# 4-up.net
KiCad netlist of a schematic drawn in EAGLE
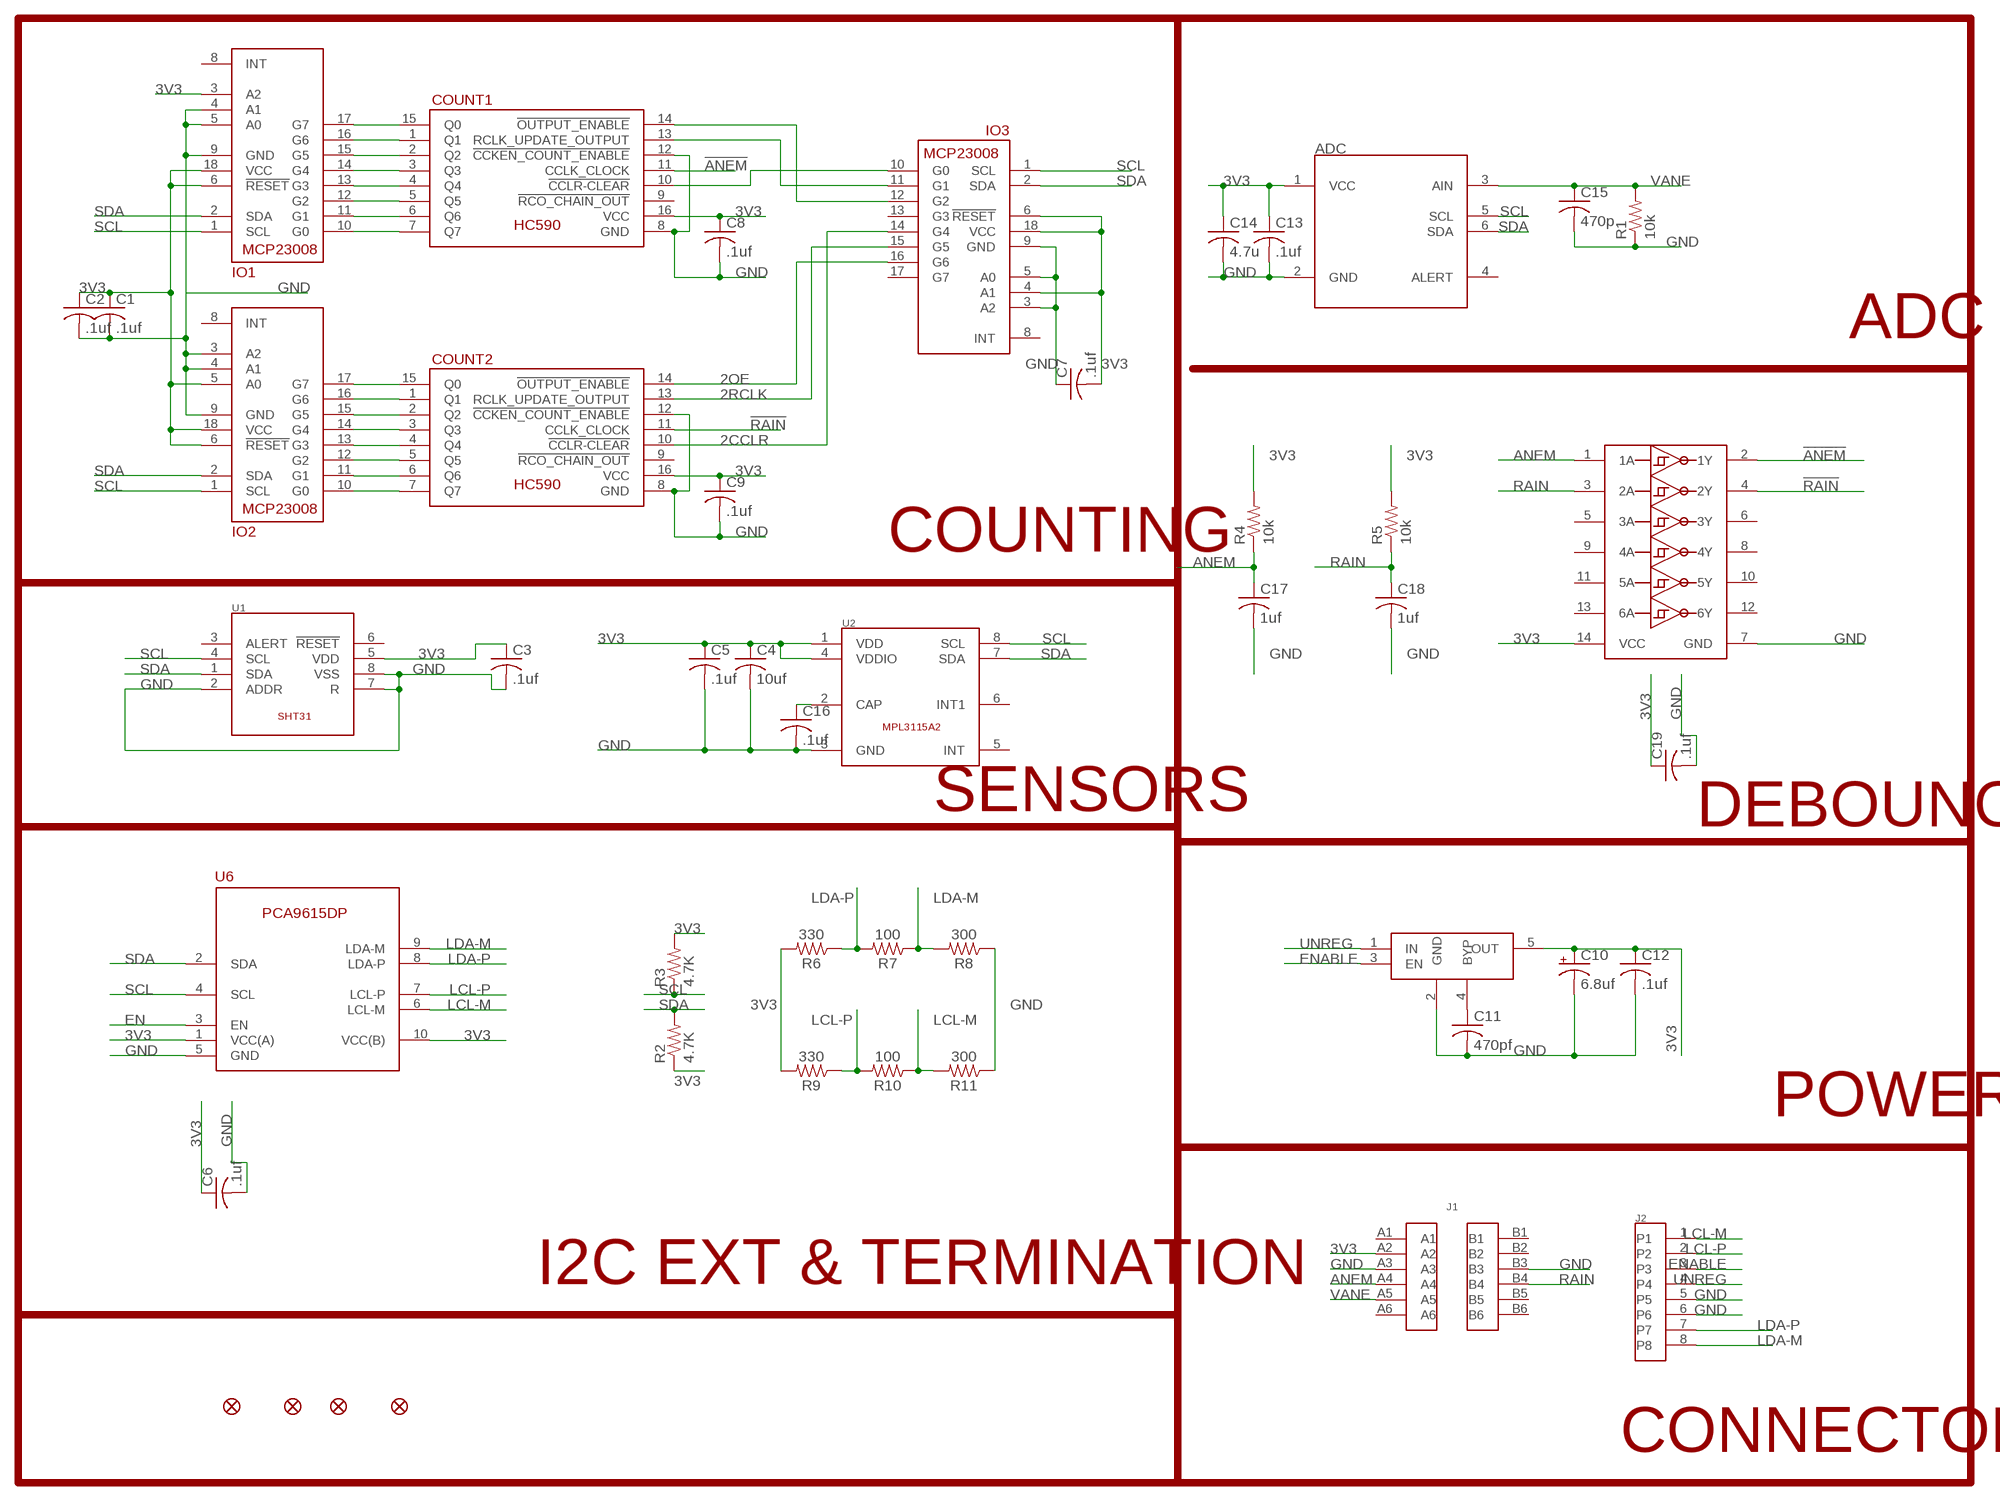
[diagram p0: schematic, sheet 1]

(export (version "E")
  (design (tool "Eeschema 10.0.6"))
  (components
    (comp (ref "ADC")
      (value "ADC081C021SOT-DDC")
      (footprint "eagle-import:SOP95P280X110-6")
      (libsource (lib "eagle-import") (part "ADC081C021SOT-DDC"))
    )
    (comp (ref "C1")
      (value ".1uf")
      (footprint "eagle-import:C0603K")
      (libsource (lib "eagle-import") (part "C-USC0603K"))
    )
    (comp (ref "C2")
      (value ".1uf")
      (footprint "eagle-import:C0603K")
      (libsource (lib "eagle-import") (part "C-USC0603K"))
    )
    (comp (ref "C3")
      (value ".1uf")
      (footprint "eagle-import:C0603K")
      (libsource (lib "eagle-import") (part "C-USC0603K"))
    )
    (comp (ref "C4")
      (value "10uf")
      (footprint "eagle-import:C0603K")
      (libsource (lib "eagle-import") (part "C-USC0603K"))
    )
    (comp (ref "C5")
      (value ".1uf")
      (footprint "eagle-import:C0603K")
      (libsource (lib "eagle-import") (part "C-USC0603K"))
    )
    (comp (ref "C6")
      (value ".1uf")
      (footprint "eagle-import:C0603K")
      (libsource (lib "eagle-import") (part "C-USC0603K"))
    )
    (comp (ref "C7")
      (value ".1uf")
      (footprint "eagle-import:C0603K")
      (libsource (lib "eagle-import") (part "C-USC0603K"))
    )
    (comp (ref "C8")
      (value ".1uf")
      (footprint "eagle-import:C0603K")
      (libsource (lib "eagle-import") (part "C-USC0603K"))
    )
    (comp (ref "C9")
      (value ".1uf")
      (footprint "eagle-import:C0603K")
      (libsource (lib "eagle-import") (part "C-USC0603K"))
    )
    (comp (ref "C10")
      (value "6.8uf")
      (footprint "eagle-import:A_3216-18R")
      (libsource (lib "eagle-import") (part "CPOL-USA/3216-18R"))
    )
    (comp (ref "C11")
      (value "470pf")
      (footprint "eagle-import:C0603K")
      (libsource (lib "eagle-import") (part "C-USC0603K"))
    )
    (comp (ref "C12")
      (value ".1uf")
      (footprint "eagle-import:C0603K")
      (libsource (lib "eagle-import") (part "C-USC0603K"))
    )
    (comp (ref "C13")
      (value ".1uf")
      (footprint "eagle-import:C0603K")
      (libsource (lib "eagle-import") (part "C-USC0603K"))
    )
    (comp (ref "C14")
      (value "4.7u")
      (footprint "eagle-import:C0603K")
      (libsource (lib "eagle-import") (part "C-USC0603K"))
    )
    (comp (ref "C15")
      (value "470p")
      (footprint "eagle-import:C0603K")
      (libsource (lib "eagle-import") (part "C-USC0603K"))
    )
    (comp (ref "C16")
      (value ".1uf")
      (footprint "eagle-import:C0603K")
      (libsource (lib "eagle-import") (part "C-USC0603K"))
    )
    (comp (ref "C17")
      (value "1uf")
      (footprint "eagle-import:C0603K")
      (libsource (lib "eagle-import") (part "C-USC0603K"))
    )
    (comp (ref "C18")
      (value "1uf")
      (footprint "eagle-import:C0603K")
      (libsource (lib "eagle-import") (part "C-USC0603K"))
    )
    (comp (ref "C19")
      (value ".1uf")
      (footprint "eagle-import:C0603K")
      (libsource (lib "eagle-import") (part "C-USC0603K"))
    )
    (comp (ref "COUNT1")
      (value "74HC590")
      (footprint "eagle-import:SOIC127P1050X265-16")
      (libsource (lib "eagle-import") (part "74HC590"))
    )
    (comp (ref "COUNT2")
      (value "74HC590")
      (footprint "eagle-import:SOIC127P1050X265-16")
      (libsource (lib "eagle-import") (part "74HC590"))
    )
    (comp (ref "FID1")
      (value "FIDUCIAL1X2.5")
      (footprint "eagle-import:FIDUCIAL-1X2.5")
      (libsource (lib "eagle-import") (part "FIDUCIAL1X2.5"))
    )
    (comp (ref "FID2")
      (value "FIDUCIAL1X2.5")
      (footprint "eagle-import:FIDUCIAL-1X2.5")
      (libsource (lib "eagle-import") (part "FIDUCIAL1X2.5"))
    )
    (comp (ref "FID3")
      (value "FIDUCIAL1X2.5")
      (footprint "eagle-import:FIDUCIAL-1X2.5")
      (libsource (lib "eagle-import") (part "FIDUCIAL1X2.5"))
    )
    (comp (ref "FID4")
      (value "FIDUCIAL1X2.5")
      (footprint "eagle-import:FIDUCIAL-1X2.5")
      (libsource (lib "eagle-import") (part "FIDUCIAL1X2.5"))
    )
    (comp (ref "INVERTER")
      (value "74HC14")
      (footprint "eagle-import:SOIC127P780X200-14")
      (libsource (lib "eagle-import") (part "74HC14"))
    )
    (comp (ref "IO1")
      (value "MCP23008")
      (footprint "eagle-import:SOIC18-W")
      (libsource (lib "eagle-import") (part "MCP23008"))
    )
    (comp (ref "IO2")
      (value "MCP23008")
      (footprint "eagle-import:SOIC18-W")
      (libsource (lib "eagle-import") (part "MCP23008"))
    )
    (comp (ref "IO3")
      (value "MCP23008")
      (footprint "eagle-import:SOIC18-W")
      (libsource (lib "eagle-import") (part "MCP23008"))
    )
    (comp (ref "J1")
      (value "43841-0005")
      (footprint "eagle-import:43841-0005")
      (libsource (lib "eagle-import") (part "43841-0005"))
    )
    (comp (ref "J2")
      (value "95501-6889")
      (footprint "eagle-import:95501-6889")
      (libsource (lib "eagle-import") (part "95501-6889"))
    )
    (comp (ref "R1")
      (value "10k")
      (footprint "eagle-import:R0603")
      (libsource (lib "eagle-import") (part "R-US_R0603"))
    )
    (comp (ref "R2")
      (value "4.7K")
      (footprint "eagle-import:R0603")
      (libsource (lib "eagle-import") (part "R-US_R0603"))
    )
    (comp (ref "R3")
      (value "4.7K")
      (footprint "eagle-import:R0603")
      (libsource (lib "eagle-import") (part "R-US_R0603"))
    )
    (comp (ref "R4")
      (value "10k")
      (footprint "eagle-import:R0603")
      (libsource (lib "eagle-import") (part "R-US_R0603"))
    )
    (comp (ref "R5")
      (value "10k")
      (footprint "eagle-import:R0603")
      (libsource (lib "eagle-import") (part "R-US_R0603"))
    )
    (comp (ref "R6")
      (value "330")
      (footprint "eagle-import:0603")
      (libsource (lib "eagle-import") (part "100KOHM-0603-1/10W-1%"))
    )
    (comp (ref "R7")
      (value "100")
      (footprint "eagle-import:0603")
      (libsource (lib "eagle-import") (part "100KOHM-0603-1/10W-1%"))
    )
    (comp (ref "R8")
      (value "300")
      (footprint "eagle-import:0603")
      (libsource (lib "eagle-import") (part "100KOHM-0603-1/10W-1%"))
    )
    (comp (ref "R9")
      (value "330")
      (footprint "eagle-import:0603")
      (libsource (lib "eagle-import") (part "100KOHM-0603-1/10W-1%"))
    )
    (comp (ref "R10")
      (value "100")
      (footprint "eagle-import:0603")
      (libsource (lib "eagle-import") (part "100KOHM-0603-1/10W-1%"))
    )
    (comp (ref "R11")
      (value "300")
      (footprint "eagle-import:0603")
      (libsource (lib "eagle-import") (part "100KOHM-0603-1/10W-1%"))
    )
    (comp (ref "U1")
      (value "SHT31")
      (footprint "eagle-import:SON50P240X240X80-9T80")
      (libsource (lib "eagle-import") (part "SHT31"))
    )
    (comp (ref "U2")
      (value "MPL3115A2LGA8")
      (footprint "eagle-import:SON125P300X500X110-8")
      (libsource (lib "eagle-import") (part "MPL3115A2LGA8"))
    )
    (comp (ref "U5")
      (value "MIC5219-3.3YM5-TR")
      (footprint "eagle-import:SOT95P280X145-5")
      (libsource (lib "eagle-import") (part "MIC5219-3.3YM5-TR"))
    )
    (comp (ref "U6")
      (value "PCA9615")
      (footprint "eagle-import:SOP50P490X110-10")
      (libsource (lib "eagle-import") (part "PCA9615"))
    )
  )
  (nets
    (net (code "1") (name "/2CCLR") (class "Default")
      (node (ref "COUNT2") (pin "10") (pinfunction "~{CCLR-CLEAR}_10") (pintype "bidirectional"))
      (node (ref "IO3") (pin "14") (pinfunction "G4_14") (pintype "bidirectional"))
    )
    (net (code "2") (name "/2OE") (class "Default")
      (node (ref "COUNT2") (pin "14") (pinfunction "~{OUTPUT_ENABLE}_14") (pintype "bidirectional"))
      (node (ref "IO3") (pin "16") (pinfunction "G6_16") (pintype "bidirectional"))
    )
    (net (code "3") (name "/2RCLK") (class "Default")
      (node (ref "COUNT2") (pin "13") (pinfunction "RCLK_UPDATE_OUTPUT_13") (pintype "bidirectional"))
      (node (ref "IO3") (pin "15") (pinfunction "G5_15") (pintype "bidirectional"))
    )
    (net (code "4") (name "/3V3") (class "Default")
      (node (ref "ADC") (pin "1") (pinfunction "VCC_1") (pintype "bidirectional"))
      (node (ref "C1") (pin "1") (pinfunction "1_1") (pintype "passive"))
      (node (ref "C10") (pin "+") (pinfunction "+_+") (pintype "passive"))
      (node (ref "C12") (pin "1") (pinfunction "1_1") (pintype "passive"))
      (node (ref "C13") (pin "1") (pinfunction "1_1") (pintype "passive"))
      (node (ref "C14") (pin "1") (pinfunction "1_1") (pintype "passive"))
      (node (ref "C19") (pin "1") (pinfunction "1_1") (pintype "passive"))
      (node (ref "C2") (pin "1") (pinfunction "1_1") (pintype "passive"))
      (node (ref "C3") (pin "1") (pinfunction "1_1") (pintype "passive"))
      (node (ref "C4") (pin "1") (pinfunction "1_1") (pintype "passive"))
      (node (ref "C5") (pin "1") (pinfunction "1_1") (pintype "passive"))
      (node (ref "C6") (pin "1") (pinfunction "1_1") (pintype "passive"))
      (node (ref "C7") (pin "2") (pinfunction "2_2") (pintype "passive"))
      (node (ref "C8") (pin "1") (pinfunction "1_1") (pintype "passive"))
      (node (ref "C9") (pin "1") (pinfunction "1_1") (pintype "passive"))
      (node (ref "COUNT1") (pin "16") (pinfunction "VCC_16") (pintype "bidirectional"))
      (node (ref "COUNT2") (pin "16") (pinfunction "VCC_16") (pintype "bidirectional"))
      (node (ref "INVERTER") (pin "14") (pinfunction "VCC_14") (pintype "bidirectional"))
      (node (ref "IO1") (pin "18") (pinfunction "VCC_18") (pintype "bidirectional"))
      (node (ref "IO1") (pin "3") (pinfunction "A2_3") (pintype "bidirectional"))
      (node (ref "IO1") (pin "6") (pinfunction "~{RESET}_6") (pintype "bidirectional"))
      (node (ref "IO2") (pin "18") (pinfunction "VCC_18") (pintype "bidirectional"))
      (node (ref "IO2") (pin "5") (pinfunction "A0_5") (pintype "bidirectional"))
      (node (ref "IO2") (pin "6") (pinfunction "~{RESET}_6") (pintype "bidirectional"))
      (node (ref "IO3") (pin "18") (pinfunction "VCC_18") (pintype "bidirectional"))
      (node (ref "IO3") (pin "4") (pinfunction "A1_4") (pintype "bidirectional"))
      (node (ref "IO3") (pin "6") (pinfunction "~{RESET}_6") (pintype "bidirectional"))
      (node (ref "J1") (pin "A2") (pinfunction "A2_A2") (pintype "bidirectional"))
      (node (ref "R2") (pin "1") (pinfunction "1_1") (pintype "passive"))
      (node (ref "R3") (pin "2") (pinfunction "2_2") (pintype "passive"))
      (node (ref "R4") (pin "2") (pinfunction "2_2") (pintype "passive"))
      (node (ref "R5") (pin "2") (pinfunction "2_2") (pintype "passive"))
      (node (ref "R6") (pin "2") (pinfunction "2_2") (pintype "passive"))
      (node (ref "R9") (pin "2") (pinfunction "2_2") (pintype "passive"))
      (node (ref "U1") (pin "5") (pinfunction "VDD_5") (pintype "bidirectional"))
      (node (ref "U2") (pin "1") (pinfunction "VDD_1") (pintype "bidirectional"))
      (node (ref "U2") (pin "4") (pinfunction "VDDIO_4") (pintype "bidirectional"))
      (node (ref "U5") (pin "5") (pinfunction "OUT_5") (pintype "bidirectional"))
      (node (ref "U6") (pin "1") (pinfunction "VCC(A)_1") (pintype "bidirectional"))
      (node (ref "U6") (pin "10") (pinfunction "VCC(B)_10") (pintype "bidirectional"))
    )
    (net (code "5") (name "/ANEM") (class "Default")
      (node (ref "C17") (pin "1") (pinfunction "1_1") (pintype "passive"))
      (node (ref "INVERTER") (pin "1") (pinfunction "1A_1") (pintype "bidirectional"))
      (node (ref "J1") (pin "A4") (pinfunction "A4_A4") (pintype "bidirectional"))
      (node (ref "R4") (pin "1") (pinfunction "1_1") (pintype "passive"))
    )
    (net (code "6") (name "/EN") (class "Default")
      (node (ref "U6") (pin "3") (pinfunction "EN_3") (pintype "bidirectional"))
    )
    (net (code "7") (name "/ENABLE") (class "Default")
      (node (ref "J2") (pin "3") (pinfunction "P3_3") (pintype "bidirectional"))
      (node (ref "U5") (pin "3") (pinfunction "EN_3") (pintype "bidirectional"))
    )
    (net (code "8") (name "/GND") (class "Default")
      (node (ref "ADC") (pin "2") (pinfunction "GND_2") (pintype "bidirectional"))
      (node (ref "C1") (pin "2") (pinfunction "2_2") (pintype "passive"))
      (node (ref "C10") (pin "-") (pinfunction "-_-") (pintype "passive"))
      (node (ref "C11") (pin "2") (pinfunction "2_2") (pintype "passive"))
      (node (ref "C12") (pin "2") (pinfunction "2_2") (pintype "passive"))
      (node (ref "C13") (pin "2") (pinfunction "2_2") (pintype "passive"))
      (node (ref "C14") (pin "2") (pinfunction "2_2") (pintype "passive"))
      (node (ref "C15") (pin "2") (pinfunction "2_2") (pintype "passive"))
      (node (ref "C16") (pin "2") (pinfunction "2_2") (pintype "passive"))
      (node (ref "C17") (pin "2") (pinfunction "2_2") (pintype "passive"))
      (node (ref "C18") (pin "2") (pinfunction "2_2") (pintype "passive"))
      (node (ref "C19") (pin "2") (pinfunction "2_2") (pintype "passive"))
      (node (ref "C2") (pin "2") (pinfunction "2_2") (pintype "passive"))
      (node (ref "C3") (pin "2") (pinfunction "2_2") (pintype "passive"))
      (node (ref "C4") (pin "2") (pinfunction "2_2") (pintype "passive"))
      (node (ref "C5") (pin "2") (pinfunction "2_2") (pintype "passive"))
      (node (ref "C6") (pin "2") (pinfunction "2_2") (pintype "passive"))
      (node (ref "C7") (pin "1") (pinfunction "1_1") (pintype "passive"))
      (node (ref "C8") (pin "2") (pinfunction "2_2") (pintype "passive"))
      (node (ref "C9") (pin "2") (pinfunction "2_2") (pintype "passive"))
      (node (ref "COUNT1") (pin "12") (pinfunction "~{CCKEN_COUNT_ENABLE}_12") (pintype "bidirectional"))
      (node (ref "COUNT1") (pin "8") (pinfunction "GND_8") (pintype "bidirectional"))
      (node (ref "COUNT2") (pin "12") (pinfunction "~{CCKEN_COUNT_ENABLE}_12") (pintype "bidirectional"))
      (node (ref "COUNT2") (pin "8") (pinfunction "GND_8") (pintype "bidirectional"))
      (node (ref "INVERTER") (pin "7") (pinfunction "GND_7") (pintype "bidirectional"))
      (node (ref "IO1") (pin "4") (pinfunction "A1_4") (pintype "bidirectional"))
      (node (ref "IO1") (pin "5") (pinfunction "A0_5") (pintype "bidirectional"))
      (node (ref "IO1") (pin "9") (pinfunction "GND_9") (pintype "bidirectional"))
      (node (ref "IO2") (pin "3") (pinfunction "A2_3") (pintype "bidirectional"))
      (node (ref "IO2") (pin "4") (pinfunction "A1_4") (pintype "bidirectional"))
      (node (ref "IO2") (pin "9") (pinfunction "GND_9") (pintype "bidirectional"))
      (node (ref "IO3") (pin "3") (pinfunction "A2_3") (pintype "bidirectional"))
      (node (ref "IO3") (pin "5") (pinfunction "A0_5") (pintype "bidirectional"))
      (node (ref "IO3") (pin "9") (pinfunction "GND_9") (pintype "bidirectional"))
      (node (ref "J1") (pin "A3") (pinfunction "A3_A3") (pintype "bidirectional"))
      (node (ref "J1") (pin "B3") (pinfunction "B3_B3") (pintype "bidirectional"))
      (node (ref "J2") (pin "5") (pinfunction "P5_5") (pintype "bidirectional"))
      (node (ref "J2") (pin "6") (pinfunction "P6_6") (pintype "bidirectional"))
      (node (ref "R1") (pin "1") (pinfunction "1_1") (pintype "passive"))
      (node (ref "R11") (pin "1") (pinfunction "1_1") (pintype "passive"))
      (node (ref "R8") (pin "1") (pinfunction "1_1") (pintype "passive"))
      (node (ref "U1") (pin "2") (pinfunction "ADDR_2") (pintype "bidirectional"))
      (node (ref "U1") (pin "7") (pinfunction "R_7") (pintype "bidirectional"))
      (node (ref "U1") (pin "8") (pinfunction "VSS_8") (pintype "bidirectional"))
      (node (ref "U2") (pin "3") (pinfunction "GND_3") (pintype "bidirectional"))
      (node (ref "U5") (pin "2") (pinfunction "GND_2") (pintype "bidirectional"))
      (node (ref "U6") (pin "5") (pinfunction "GND_5") (pintype "bidirectional"))
    )
    (net (code "9") (name "/LCL-M") (class "Default")
      (node (ref "J2") (pin "1") (pinfunction "P1_1") (pintype "bidirectional"))
      (node (ref "R10") (pin "1") (pinfunction "1_1") (pintype "passive"))
      (node (ref "R11") (pin "2") (pinfunction "2_2") (pintype "passive"))
      (node (ref "U6") (pin "6") (pinfunction "LCL-M_6") (pintype "bidirectional"))
    )
    (net (code "10") (name "/LCL-P") (class "Default")
      (node (ref "J2") (pin "2") (pinfunction "P2_2") (pintype "bidirectional"))
      (node (ref "R10") (pin "2") (pinfunction "2_2") (pintype "passive"))
      (node (ref "R9") (pin "1") (pinfunction "1_1") (pintype "passive"))
      (node (ref "U6") (pin "7") (pinfunction "LCL-P_7") (pintype "bidirectional"))
    )
    (net (code "11") (name "/LDA-M") (class "Default")
      (node (ref "J2") (pin "8") (pinfunction "P8_8") (pintype "bidirectional"))
      (node (ref "R7") (pin "1") (pinfunction "1_1") (pintype "passive"))
      (node (ref "R8") (pin "2") (pinfunction "2_2") (pintype "passive"))
      (node (ref "U6") (pin "9") (pinfunction "LDA-M_9") (pintype "bidirectional"))
    )
    (net (code "12") (name "/LDA-P") (class "Default")
      (node (ref "J2") (pin "7") (pinfunction "P7_7") (pintype "bidirectional"))
      (node (ref "R6") (pin "1") (pinfunction "1_1") (pintype "passive"))
      (node (ref "R7") (pin "2") (pinfunction "2_2") (pintype "passive"))
      (node (ref "U6") (pin "8") (pinfunction "LDA-P_8") (pintype "bidirectional"))
    )
    (net (code "13") (name "/RAIN") (class "Default")
      (node (ref "C18") (pin "1") (pinfunction "1_1") (pintype "passive"))
      (node (ref "INVERTER") (pin "3") (pinfunction "2A_3") (pintype "bidirectional"))
      (node (ref "J1") (pin "B4") (pinfunction "B4_B4") (pintype "bidirectional"))
      (node (ref "R5") (pin "1") (pinfunction "1_1") (pintype "passive"))
    )
    (net (code "14") (name "/SCL") (class "Default")
      (node (ref "ADC") (pin "5") (pinfunction "SCL_5") (pintype "bidirectional"))
      (node (ref "IO1") (pin "1") (pinfunction "SCL_1") (pintype "bidirectional"))
      (node (ref "IO2") (pin "1") (pinfunction "SCL_1") (pintype "bidirectional"))
      (node (ref "IO3") (pin "1") (pinfunction "SCL_1") (pintype "bidirectional"))
      (node (ref "R3") (pin "1") (pinfunction "1_1") (pintype "passive"))
      (node (ref "U1") (pin "4") (pinfunction "SCL_4") (pintype "bidirectional"))
      (node (ref "U2") (pin "8") (pinfunction "SCL_8") (pintype "bidirectional"))
      (node (ref "U6") (pin "4") (pinfunction "SCL_4") (pintype "bidirectional"))
    )
    (net (code "15") (name "/SDA") (class "Default")
      (node (ref "ADC") (pin "6") (pinfunction "SDA_6") (pintype "bidirectional"))
      (node (ref "IO1") (pin "2") (pinfunction "SDA_2") (pintype "bidirectional"))
      (node (ref "IO2") (pin "2") (pinfunction "SDA_2") (pintype "bidirectional"))
      (node (ref "IO3") (pin "2") (pinfunction "SDA_2") (pintype "bidirectional"))
      (node (ref "R2") (pin "2") (pinfunction "2_2") (pintype "passive"))
      (node (ref "U1") (pin "1") (pinfunction "SDA_1") (pintype "bidirectional"))
      (node (ref "U2") (pin "7") (pinfunction "SDA_7") (pintype "bidirectional"))
      (node (ref "U6") (pin "2") (pinfunction "SDA_2") (pintype "bidirectional"))
    )
    (net (code "16") (name "/UNREG") (class "Default")
      (node (ref "J2") (pin "4") (pinfunction "P4_4") (pintype "bidirectional"))
      (node (ref "U5") (pin "1") (pinfunction "IN_1") (pintype "bidirectional"))
    )
    (net (code "17") (name "/VANE") (class "Default")
      (node (ref "ADC") (pin "3") (pinfunction "AIN_3") (pintype "bidirectional"))
      (node (ref "C15") (pin "1") (pinfunction "1_1") (pintype "passive"))
      (node (ref "J1") (pin "A5") (pinfunction "A5_A5") (pintype "bidirectional"))
      (node (ref "R1") (pin "2") (pinfunction "2_2") (pintype "passive"))
    )
    (net (code "18") (name "/~{ANEM}") (class "Default")
      (node (ref "COUNT1") (pin "11") (pinfunction "CCLK_CLOCK_11") (pintype "bidirectional"))
      (node (ref "INVERTER") (pin "2") (pinfunction "1Y_2") (pintype "bidirectional"))
    )
    (net (code "19") (name "/~{RAIN}") (class "Default")
      (node (ref "COUNT2") (pin "11") (pinfunction "CCLK_CLOCK_11") (pintype "bidirectional"))
      (node (ref "INVERTER") (pin "4") (pinfunction "2Y_4") (pintype "bidirectional"))
    )
    (net (code "20") (name "Net-(COUNT1-Q0)") (class "Default")
      (node (ref "COUNT1") (pin "15") (pinfunction "Q0_15") (pintype "bidirectional"))
      (node (ref "IO1") (pin "17") (pinfunction "G7_17") (pintype "bidirectional"))
    )
    (net (code "21") (name "Net-(COUNT1-Q1)") (class "Default")
      (node (ref "COUNT1") (pin "1") (pinfunction "Q1_1") (pintype "bidirectional"))
      (node (ref "IO1") (pin "16") (pinfunction "G6_16") (pintype "bidirectional"))
    )
    (net (code "22") (name "Net-(COUNT1-Q2)") (class "Default")
      (node (ref "COUNT1") (pin "2") (pinfunction "Q2_2") (pintype "bidirectional"))
      (node (ref "IO1") (pin "15") (pinfunction "G5_15") (pintype "bidirectional"))
    )
    (net (code "23") (name "Net-(COUNT1-Q3)") (class "Default")
      (node (ref "COUNT1") (pin "3") (pinfunction "Q3_3") (pintype "bidirectional"))
      (node (ref "IO1") (pin "14") (pinfunction "G4_14") (pintype "bidirectional"))
    )
    (net (code "24") (name "Net-(COUNT1-Q4)") (class "Default")
      (node (ref "COUNT1") (pin "4") (pinfunction "Q4_4") (pintype "bidirectional"))
      (node (ref "IO1") (pin "13") (pinfunction "G3_13") (pintype "bidirectional"))
    )
    (net (code "25") (name "Net-(COUNT1-Q5)") (class "Default")
      (node (ref "COUNT1") (pin "5") (pinfunction "Q5_5") (pintype "bidirectional"))
      (node (ref "IO1") (pin "12") (pinfunction "G2_12") (pintype "bidirectional"))
    )
    (net (code "26") (name "Net-(COUNT1-Q6)") (class "Default")
      (node (ref "COUNT1") (pin "6") (pinfunction "Q6_6") (pintype "bidirectional"))
      (node (ref "IO1") (pin "11") (pinfunction "G1_11") (pintype "bidirectional"))
    )
    (net (code "27") (name "Net-(COUNT1-Q7)") (class "Default")
      (node (ref "COUNT1") (pin "7") (pinfunction "Q7_7") (pintype "bidirectional"))
      (node (ref "IO1") (pin "10") (pinfunction "G0_10") (pintype "bidirectional"))
    )
    (net (code "28") (name "Net-(COUNT1-RCLK_UPDATE_OUTPUT)") (class "Default")
      (node (ref "COUNT1") (pin "13") (pinfunction "RCLK_UPDATE_OUTPUT_13") (pintype "bidirectional"))
      (node (ref "IO3") (pin "11") (pinfunction "G1_11") (pintype "bidirectional"))
    )
    (net (code "29") (name "Net-(COUNT1-~{CCLR-CLEAR})") (class "Default")
      (node (ref "COUNT1") (pin "10") (pinfunction "~{CCLR-CLEAR}_10") (pintype "bidirectional"))
      (node (ref "IO3") (pin "10") (pinfunction "G0_10") (pintype "bidirectional"))
    )
    (net (code "30") (name "Net-(COUNT1-~{OUTPUT_ENABLE})") (class "Default")
      (node (ref "COUNT1") (pin "14") (pinfunction "~{OUTPUT_ENABLE}_14") (pintype "bidirectional"))
      (node (ref "IO3") (pin "12") (pinfunction "G2_12") (pintype "bidirectional"))
    )
    (net (code "31") (name "Net-(COUNT2-Q0)") (class "Default")
      (node (ref "COUNT2") (pin "15") (pinfunction "Q0_15") (pintype "bidirectional"))
      (node (ref "IO2") (pin "17") (pinfunction "G7_17") (pintype "bidirectional"))
    )
    (net (code "32") (name "Net-(COUNT2-Q1)") (class "Default")
      (node (ref "COUNT2") (pin "1") (pinfunction "Q1_1") (pintype "bidirectional"))
      (node (ref "IO2") (pin "16") (pinfunction "G6_16") (pintype "bidirectional"))
    )
    (net (code "33") (name "Net-(COUNT2-Q2)") (class "Default")
      (node (ref "COUNT2") (pin "2") (pinfunction "Q2_2") (pintype "bidirectional"))
      (node (ref "IO2") (pin "15") (pinfunction "G5_15") (pintype "bidirectional"))
    )
    (net (code "34") (name "Net-(COUNT2-Q3)") (class "Default")
      (node (ref "COUNT2") (pin "3") (pinfunction "Q3_3") (pintype "bidirectional"))
      (node (ref "IO2") (pin "14") (pinfunction "G4_14") (pintype "bidirectional"))
    )
    (net (code "35") (name "Net-(COUNT2-Q4)") (class "Default")
      (node (ref "COUNT2") (pin "4") (pinfunction "Q4_4") (pintype "bidirectional"))
      (node (ref "IO2") (pin "13") (pinfunction "G3_13") (pintype "bidirectional"))
    )
    (net (code "36") (name "Net-(COUNT2-Q5)") (class "Default")
      (node (ref "COUNT2") (pin "5") (pinfunction "Q5_5") (pintype "bidirectional"))
      (node (ref "IO2") (pin "12") (pinfunction "G2_12") (pintype "bidirectional"))
    )
    (net (code "37") (name "Net-(COUNT2-Q6)") (class "Default")
      (node (ref "COUNT2") (pin "6") (pinfunction "Q6_6") (pintype "bidirectional"))
      (node (ref "IO2") (pin "11") (pinfunction "G1_11") (pintype "bidirectional"))
    )
    (net (code "38") (name "Net-(COUNT2-Q7)") (class "Default")
      (node (ref "COUNT2") (pin "7") (pinfunction "Q7_7") (pintype "bidirectional"))
      (node (ref "IO2") (pin "10") (pinfunction "G0_10") (pintype "bidirectional"))
    )
    (net (code "39") (name "Net-(U2-CAP)") (class "Default")
      (node (ref "C16") (pin "1") (pinfunction "1_1") (pintype "passive"))
      (node (ref "U2") (pin "2") (pinfunction "CAP_2") (pintype "bidirectional"))
    )
    (net (code "40") (name "Net-(U5-BYP)") (class "Default")
      (node (ref "C11") (pin "1") (pinfunction "1_1") (pintype "passive"))
      (node (ref "U5") (pin "4") (pinfunction "BYP_4") (pintype "bidirectional"))
    )
    (net (code "41") (name "unconnected-(ADC-ALERT-Pad4)") (class "Default")
      (node (ref "ADC") (pin "4") (pinfunction "ALERT_4") (pintype "bidirectional"))
    )
    (net (code "42") (name "unconnected-(COUNT1-~{RCO_CHAIN_OUT}-Pad9)") (class "Default")
      (node (ref "COUNT1") (pin "9") (pinfunction "~{RCO_CHAIN_OUT}_9") (pintype "bidirectional"))
    )
    (net (code "43") (name "unconnected-(COUNT2-~{RCO_CHAIN_OUT}-Pad9)") (class "Default")
      (node (ref "COUNT2") (pin "9") (pinfunction "~{RCO_CHAIN_OUT}_9") (pintype "bidirectional"))
    )
    (net (code "44") (name "unconnected-(INVERTER-3A-Pad5)") (class "Default")
      (node (ref "INVERTER") (pin "5") (pinfunction "3A_5") (pintype "bidirectional"))
    )
    (net (code "45") (name "unconnected-(INVERTER-3Y-Pad6)") (class "Default")
      (node (ref "INVERTER") (pin "6") (pinfunction "3Y_6") (pintype "bidirectional"))
    )
    (net (code "46") (name "unconnected-(INVERTER-4A-Pad9)") (class "Default")
      (node (ref "INVERTER") (pin "9") (pinfunction "4A_9") (pintype "bidirectional"))
    )
    (net (code "47") (name "unconnected-(INVERTER-4Y-Pad8)") (class "Default")
      (node (ref "INVERTER") (pin "8") (pinfunction "4Y_8") (pintype "bidirectional"))
    )
    (net (code "48") (name "unconnected-(INVERTER-5A-Pad11)") (class "Default")
      (node (ref "INVERTER") (pin "11") (pinfunction "5A_11") (pintype "bidirectional"))
    )
    (net (code "49") (name "unconnected-(INVERTER-5Y-Pad10)") (class "Default")
      (node (ref "INVERTER") (pin "10") (pinfunction "5Y_10") (pintype "bidirectional"))
    )
    (net (code "50") (name "unconnected-(INVERTER-6A-Pad13)") (class "Default")
      (node (ref "INVERTER") (pin "13") (pinfunction "6A_13") (pintype "bidirectional"))
    )
    (net (code "51") (name "unconnected-(INVERTER-6Y-Pad12)") (class "Default")
      (node (ref "INVERTER") (pin "12") (pinfunction "6Y_12") (pintype "bidirectional"))
    )
    (net (code "52") (name "unconnected-(IO1-INT-Pad8)") (class "Default")
      (node (ref "IO1") (pin "8") (pinfunction "INT_8") (pintype "bidirectional"))
    )
    (net (code "53") (name "unconnected-(IO2-INT-Pad8)") (class "Default")
      (node (ref "IO2") (pin "8") (pinfunction "INT_8") (pintype "bidirectional"))
    )
    (net (code "54") (name "unconnected-(IO3-G3-Pad13)") (class "Default")
      (node (ref "IO3") (pin "13") (pinfunction "G3_13") (pintype "bidirectional"))
    )
    (net (code "55") (name "unconnected-(IO3-G7-Pad17)") (class "Default")
      (node (ref "IO3") (pin "17") (pinfunction "G7_17") (pintype "bidirectional"))
    )
    (net (code "56") (name "unconnected-(IO3-INT-Pad8)") (class "Default")
      (node (ref "IO3") (pin "8") (pinfunction "INT_8") (pintype "bidirectional"))
    )
    (net (code "57") (name "unconnected-(J1-PadA1)") (class "Default")
      (node (ref "J1") (pin "A1") (pinfunction "A1_A1") (pintype "bidirectional"))
    )
    (net (code "58") (name "unconnected-(J1-PadA6)") (class "Default")
      (node (ref "J1") (pin "A6") (pinfunction "A6_A6") (pintype "bidirectional"))
    )
    (net (code "59") (name "unconnected-(J1-PadB1)") (class "Default")
      (node (ref "J1") (pin "B1") (pinfunction "B1_B1") (pintype "bidirectional"))
    )
    (net (code "60") (name "unconnected-(J1-PadB2)") (class "Default")
      (node (ref "J1") (pin "B2") (pinfunction "B2_B2") (pintype "bidirectional"))
    )
    (net (code "61") (name "unconnected-(J1-PadB5)") (class "Default")
      (node (ref "J1") (pin "B5") (pinfunction "B5_B5") (pintype "bidirectional"))
    )
    (net (code "62") (name "unconnected-(J1-PadB6)") (class "Default")
      (node (ref "J1") (pin "B6") (pinfunction "B6_B6") (pintype "bidirectional"))
    )
    (net (code "63") (name "unconnected-(U1-ALERT-Pad3)") (class "Default")
      (node (ref "U1") (pin "3") (pinfunction "ALERT_3") (pintype "bidirectional"))
    )
    (net (code "64") (name "unconnected-(U1-~{RESET}-Pad6)") (class "Default")
      (node (ref "U1") (pin "6") (pinfunction "~{RESET}_6") (pintype "bidirectional"))
    )
    (net (code "65") (name "unconnected-(U2-INT-Pad5)") (class "Default")
      (node (ref "U2") (pin "5") (pinfunction "INT_5") (pintype "bidirectional"))
    )
    (net (code "66") (name "unconnected-(U2-INT1-Pad6)") (class "Default")
      (node (ref "U2") (pin "6") (pinfunction "INT1_6") (pintype "bidirectional"))
    )
  )
)
